# 5_PROFIBUS2.net
KiCad netlist of a schematic drawn in Altium Designer
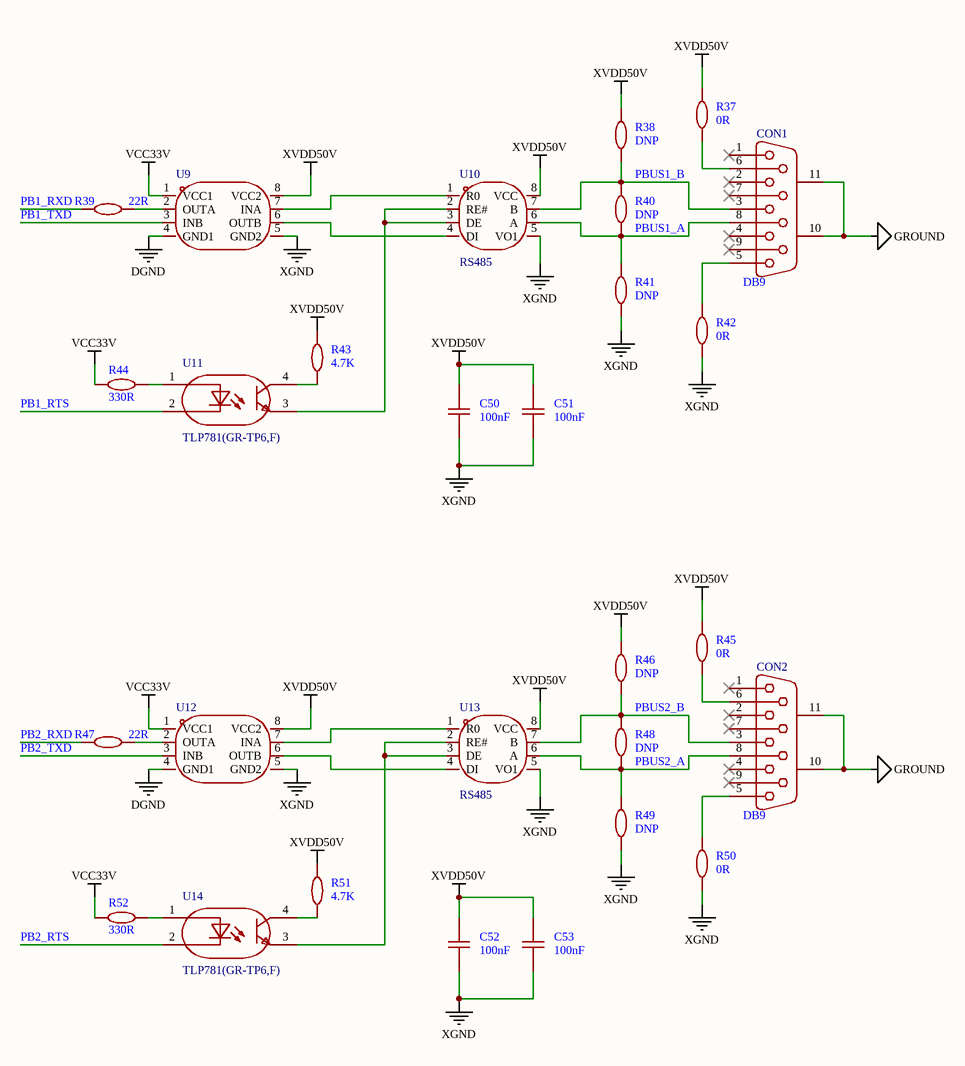
[diagram p0: 5_PROFIBUS2.schdoc]

(export (version "E")
  (design (tool "Eeschema 10.0.6"))
  (components
    (comp (ref "C50")
      (value "100nF")
      (footprint "C0402")
      (libsource (lib "altium-import") (part "root_1_CAP_0402_"))
    )
    (comp (ref "C51")
      (value "100nF")
      (footprint "C0402")
      (libsource (lib "altium-import") (part "root_1_CAP_0402_"))
    )
    (comp (ref "C52")
      (value "100nF")
      (footprint "C0402")
      (libsource (lib "altium-import") (part "root_1_CAP_0402_"))
    )
    (comp (ref "C53")
      (value "100nF")
      (footprint "C0402")
      (libsource (lib "altium-import") (part "root_1_CAP_0402_"))
    )
    (comp (ref "CON1")
      (value "DB9")
      (footprint "DB9-TH_DT10121-M5N3-4F")
      (libsource (lib "altium-import") (part "root_1_DB9 TH90_"))
    )
    (comp (ref "CON2")
      (value "DB9")
      (footprint "DB9-TH_DT10121-M5N3-4F")
      (libsource (lib "altium-import") (part "root_1_DB9 TH90_"))
    )
    (comp (ref "R37")
      (value "0R")
      (footprint "R0805")
      (libsource (lib "altium-import") (part "root_3_Res_0805_"))
    )
    (comp (ref "R38")
      (value "DNP")
      (footprint "R0805")
      (libsource (lib "altium-import") (part "root_1_Res_0805_"))
    )
    (comp (ref "R39")
      (value "22R")
      (footprint "R0402")
      (libsource (lib "altium-import") (part "root_0_Res_0402_"))
    )
    (comp (ref "R40")
      (value "DNP")
      (footprint "R0805")
      (libsource (lib "altium-import") (part "root_1_Res_0805_"))
    )
    (comp (ref "R41")
      (value "DNP")
      (footprint "R0805")
      (libsource (lib "altium-import") (part "root_1_Res_0805_"))
    )
    (comp (ref "R42")
      (value "0R")
      (footprint "R0805")
      (libsource (lib "altium-import") (part "root_1_Res_0805_"))
    )
    (comp (ref "R43")
      (value "4.7K")
      (footprint "R0402")
      (libsource (lib "altium-import") (part "root_1_Res_0402_"))
    )
    (comp (ref "R44")
      (value "330R")
      (footprint "R0402")
      (libsource (lib "altium-import") (part "root_0_Res_0402_"))
    )
    (comp (ref "R45")
      (value "0R")
      (footprint "R0805")
      (libsource (lib "altium-import") (part "root_3_Res_0805_"))
    )
    (comp (ref "R46")
      (value "DNP")
      (footprint "R0805")
      (libsource (lib "altium-import") (part "root_1_Res_0805_"))
    )
    (comp (ref "R47")
      (value "22R")
      (footprint "R0402")
      (libsource (lib "altium-import") (part "root_0_Res_0402_"))
    )
    (comp (ref "R48")
      (value "DNP")
      (footprint "R0805")
      (libsource (lib "altium-import") (part "root_1_Res_0805_"))
    )
    (comp (ref "R49")
      (value "DNP")
      (footprint "R0805")
      (libsource (lib "altium-import") (part "root_1_Res_0805_"))
    )
    (comp (ref "R50")
      (value "0R")
      (footprint "R0805")
      (libsource (lib "altium-import") (part "root_1_Res_0805_"))
    )
    (comp (ref "R51")
      (value "4.7K")
      (footprint "R0402")
      (libsource (lib "altium-import") (part "root_1_Res_0402_"))
    )
    (comp (ref "R52")
      (value "330R")
      (footprint "R0402")
      (libsource (lib "altium-import") (part "root_0_Res_0402_"))
    )
    (comp (ref "U9")
      (value "~")
      (footprint "SOIC-8_L5.0-W4.0-P1.27-LS6.0-BL")
      (libsource (lib "altium-import") (part "root_0_ISO7221AD_"))
    )
    (comp (ref "U10")
      (value "~")
      (footprint "SOP-8_L4.9-W3.9-P1.27-LS6.0-BL")
      (fields (field (name "DEVICE") "RS485"))
      (libsource (lib "altium-import") (part "root_0_RS485_"))
    )
    (comp (ref "U11")
      (value "~")
      (footprint "SOP-4_L6.5-W4.6-P2.54-LS10.3-TL")
      (fields (field (name "DEVICE") "TLP781(GR-TP6,F)"))
      (libsource (lib "altium-import") (part "root_0_TLP781(GR-TP6,F)_"))
    )
    (comp (ref "U12")
      (value "~")
      (footprint "SOIC-8_L5.0-W4.0-P1.27-LS6.0-BL")
      (libsource (lib "altium-import") (part "root_0_ISO7221AD_"))
    )
    (comp (ref "U13")
      (value "~")
      (footprint "SOP-8_L4.9-W3.9-P1.27-LS6.0-BL")
      (fields (field (name "DEVICE") "RS485"))
      (libsource (lib "altium-import") (part "root_0_RS485_"))
    )
    (comp (ref "U14")
      (value "~")
      (footprint "SOP-4_L6.5-W4.6-P2.54-LS10.3-TL")
      (fields (field (name "DEVICE") "TLP781(GR-TP6,F)"))
      (libsource (lib "altium-import") (part "root_0_TLP781(GR-TP6,F)_"))
    )
  )
  (nets
    (net (code "1") (name "/PB1_RTS") (class "Default")
      (node (ref "U11") (pin "2") (pinfunction "2_2") (pintype "passive"))
    )
    (net (code "2") (name "/PB1_RXD") (class "Default")
      (node (ref "R39") (pin "1") (pinfunction "1_1") (pintype "passive"))
    )
    (net (code "3") (name "/PB1_TXD") (class "Default")
      (node (ref "U9") (pin "3") (pinfunction "INB_3") (pintype "passive"))
    )
    (net (code "4") (name "/PB2_RTS") (class "Default")
      (node (ref "U14") (pin "2") (pinfunction "2_2") (pintype "passive"))
    )
    (net (code "5") (name "/PB2_RXD") (class "Default")
      (node (ref "R47") (pin "1") (pinfunction "1_1") (pintype "passive"))
    )
    (net (code "6") (name "/PB2_TXD") (class "Default")
      (node (ref "U12") (pin "3") (pinfunction "INB_3") (pintype "passive"))
    )
    (net (code "7") (name "/PBUS1_A") (class "Default")
      (node (ref "CON1") (pin "8") (pinfunction "8_8") (pintype "passive"))
      (node (ref "R40") (pin "1") (pinfunction "1_1") (pintype "passive"))
      (node (ref "R41") (pin "2") (pinfunction "2_2") (pintype "passive"))
      (node (ref "U10") (pin "6") (pinfunction "A_6") (pintype "passive"))
    )
    (net (code "8") (name "/PBUS1_B") (class "Default")
      (node (ref "CON1") (pin "3") (pinfunction "3_3") (pintype "passive"))
      (node (ref "R38") (pin "1") (pinfunction "1_1") (pintype "passive"))
      (node (ref "R40") (pin "2") (pinfunction "2_2") (pintype "passive"))
      (node (ref "U10") (pin "7") (pinfunction "B_7") (pintype "passive"))
    )
    (net (code "9") (name "/PBUS2_A") (class "Default")
      (node (ref "CON2") (pin "8") (pinfunction "8_8") (pintype "passive"))
      (node (ref "R48") (pin "1") (pinfunction "1_1") (pintype "passive"))
      (node (ref "R49") (pin "2") (pinfunction "2_2") (pintype "passive"))
      (node (ref "U13") (pin "6") (pinfunction "A_6") (pintype "passive"))
    )
    (net (code "10") (name "/PBUS2_B") (class "Default")
      (node (ref "CON2") (pin "3") (pinfunction "3_3") (pintype "passive"))
      (node (ref "R46") (pin "1") (pinfunction "1_1") (pintype "passive"))
      (node (ref "R48") (pin "2") (pinfunction "2_2") (pintype "passive"))
      (node (ref "U13") (pin "7") (pinfunction "B_7") (pintype "passive"))
    )
    (net (code "11") (name "DGND") (class "Default")
      (node (ref "U12") (pin "4") (pinfunction "GND1_4") (pintype "passive"))
      (node (ref "U9") (pin "4") (pinfunction "GND1_4") (pintype "passive"))
    )
    (net (code "12") (name "GROUND") (class "Default")
      (node (ref "CON1") (pin "10") (pinfunction "MH1_10") (pintype "passive"))
      (node (ref "CON1") (pin "11") (pinfunction "MH2_11") (pintype "passive"))
      (node (ref "CON2") (pin "10") (pinfunction "MH1_10") (pintype "passive"))
      (node (ref "CON2") (pin "11") (pinfunction "MH2_11") (pintype "passive"))
    )
    (net (code "13") (name "Net-(CON1-Pad5)") (class "Default")
      (node (ref "CON1") (pin "5") (pinfunction "5_5") (pintype "passive"))
      (node (ref "R42") (pin "2") (pinfunction "2_2") (pintype "passive"))
    )
    (net (code "14") (name "Net-(CON1-Pad6)") (class "Default")
      (node (ref "CON1") (pin "6") (pinfunction "6_6") (pintype "passive"))
      (node (ref "R37") (pin "2") (pinfunction "2_2") (pintype "passive"))
    )
    (net (code "15") (name "Net-(CON2-Pad5)") (class "Default")
      (node (ref "CON2") (pin "5") (pinfunction "5_5") (pintype "passive"))
      (node (ref "R50") (pin "2") (pinfunction "2_2") (pintype "passive"))
    )
    (net (code "16") (name "Net-(CON2-Pad6)") (class "Default")
      (node (ref "CON2") (pin "6") (pinfunction "6_6") (pintype "passive"))
      (node (ref "R45") (pin "2") (pinfunction "2_2") (pintype "passive"))
    )
    (net (code "17") (name "Net-(R43-Pad1)") (class "Default")
      (node (ref "R43") (pin "1") (pinfunction "1_1") (pintype "passive"))
      (node (ref "U11") (pin "4") (pinfunction "4_4") (pintype "passive"))
    )
    (net (code "18") (name "Net-(R44-Pad2)") (class "Default")
      (node (ref "R44") (pin "2") (pinfunction "2_2") (pintype "passive"))
      (node (ref "U11") (pin "1") (pinfunction "1_1") (pintype "passive"))
    )
    (net (code "19") (name "Net-(R51-Pad1)") (class "Default")
      (node (ref "R51") (pin "1") (pinfunction "1_1") (pintype "passive"))
      (node (ref "U14") (pin "4") (pinfunction "4_4") (pintype "passive"))
    )
    (net (code "20") (name "Net-(R52-Pad2)") (class "Default")
      (node (ref "R52") (pin "2") (pinfunction "2_2") (pintype "passive"))
      (node (ref "U14") (pin "1") (pinfunction "1_1") (pintype "passive"))
    )
    (net (code "21") (name "Net-(U9-OUTA)") (class "Default")
      (node (ref "R39") (pin "2") (pinfunction "2_2") (pintype "passive"))
      (node (ref "U9") (pin "2") (pinfunction "OUTA_2") (pintype "passive"))
    )
    (net (code "22") (name "Net-(U10-DE)") (class "Default")
      (node (ref "U10") (pin "2") (pinfunction "RE#_2") (pintype "passive"))
      (node (ref "U10") (pin "3") (pinfunction "DE_3") (pintype "passive"))
      (node (ref "U11") (pin "3") (pinfunction "3_3") (pintype "passive"))
    )
    (net (code "23") (name "Net-(U10-DI)") (class "Default")
      (node (ref "U10") (pin "4") (pinfunction "DI_4") (pintype "passive"))
      (node (ref "U9") (pin "6") (pinfunction "OUTB_6") (pintype "passive"))
    )
    (net (code "24") (name "Net-(U10-R0)") (class "Default")
      (node (ref "U10") (pin "1") (pinfunction "R0_1") (pintype "passive"))
      (node (ref "U9") (pin "7") (pinfunction "INA_7") (pintype "passive"))
    )
    (net (code "25") (name "Net-(U12-INA)") (class "Default")
      (node (ref "U12") (pin "7") (pinfunction "INA_7") (pintype "passive"))
      (node (ref "U13") (pin "1") (pinfunction "R0_1") (pintype "passive"))
    )
    (net (code "26") (name "Net-(U12-OUTA)") (class "Default")
      (node (ref "R47") (pin "2") (pinfunction "2_2") (pintype "passive"))
      (node (ref "U12") (pin "2") (pinfunction "OUTA_2") (pintype "passive"))
    )
    (net (code "27") (name "Net-(U12-OUTB)") (class "Default")
      (node (ref "U12") (pin "6") (pinfunction "OUTB_6") (pintype "passive"))
      (node (ref "U13") (pin "4") (pinfunction "DI_4") (pintype "passive"))
    )
    (net (code "28") (name "Net-(U13-DE)") (class "Default")
      (node (ref "U13") (pin "2") (pinfunction "RE#_2") (pintype "passive"))
      (node (ref "U13") (pin "3") (pinfunction "DE_3") (pintype "passive"))
      (node (ref "U14") (pin "3") (pinfunction "3_3") (pintype "passive"))
    )
    (net (code "29") (name "VCC33V") (class "Default")
      (node (ref "R44") (pin "1") (pinfunction "1_1") (pintype "passive"))
      (node (ref "R52") (pin "1") (pinfunction "1_1") (pintype "passive"))
      (node (ref "U12") (pin "1") (pinfunction "VCC1_1") (pintype "passive"))
      (node (ref "U9") (pin "1") (pinfunction "VCC1_1") (pintype "passive"))
    )
    (net (code "30") (name "XGND") (class "Default")
      (node (ref "C50") (pin "1") (pinfunction "1_1") (pintype "passive"))
      (node (ref "C51") (pin "1") (pinfunction "1_1") (pintype "passive"))
      (node (ref "C52") (pin "1") (pinfunction "1_1") (pintype "passive"))
      (node (ref "C53") (pin "1") (pinfunction "1_1") (pintype "passive"))
      (node (ref "R41") (pin "1") (pinfunction "1_1") (pintype "passive"))
      (node (ref "R42") (pin "1") (pinfunction "1_1") (pintype "passive"))
      (node (ref "R49") (pin "1") (pinfunction "1_1") (pintype "passive"))
      (node (ref "R50") (pin "1") (pinfunction "1_1") (pintype "passive"))
      (node (ref "U10") (pin "5") (pinfunction "VO1_5") (pintype "passive"))
      (node (ref "U12") (pin "5") (pinfunction "GND2_5") (pintype "passive"))
      (node (ref "U13") (pin "5") (pinfunction "VO1_5") (pintype "passive"))
      (node (ref "U9") (pin "5") (pinfunction "GND2_5") (pintype "passive"))
    )
    (net (code "31") (name "XVDD50V") (class "Default")
      (node (ref "C50") (pin "2") (pinfunction "2_2") (pintype "passive"))
      (node (ref "C51") (pin "2") (pinfunction "2_2") (pintype "passive"))
      (node (ref "C52") (pin "2") (pinfunction "2_2") (pintype "passive"))
      (node (ref "C53") (pin "2") (pinfunction "2_2") (pintype "passive"))
      (node (ref "R37") (pin "1") (pinfunction "1_1") (pintype "passive"))
      (node (ref "R38") (pin "2") (pinfunction "2_2") (pintype "passive"))
      (node (ref "R43") (pin "2") (pinfunction "2_2") (pintype "passive"))
      (node (ref "R45") (pin "1") (pinfunction "1_1") (pintype "passive"))
      (node (ref "R46") (pin "2") (pinfunction "2_2") (pintype "passive"))
      (node (ref "R51") (pin "2") (pinfunction "2_2") (pintype "passive"))
      (node (ref "U10") (pin "8") (pinfunction "VCC_8") (pintype "passive"))
      (node (ref "U12") (pin "8") (pinfunction "VCC2_8") (pintype "passive"))
      (node (ref "U13") (pin "8") (pinfunction "VCC_8") (pintype "passive"))
      (node (ref "U9") (pin "8") (pinfunction "VCC2_8") (pintype "passive"))
    )
    (net (code "32") (name "unconnected-(CON1-Pad1)") (class "Default")
      (node (ref "CON1") (pin "1") (pinfunction "1_1") (pintype "passive+no_connect"))
    )
    (net (code "33") (name "unconnected-(CON1-Pad2)") (class "Default")
      (node (ref "CON1") (pin "2") (pinfunction "2_2") (pintype "passive+no_connect"))
    )
    (net (code "34") (name "unconnected-(CON1-Pad4)") (class "Default")
      (node (ref "CON1") (pin "4") (pinfunction "4_4") (pintype "passive+no_connect"))
    )
    (net (code "35") (name "unconnected-(CON1-Pad7)") (class "Default")
      (node (ref "CON1") (pin "7") (pinfunction "7_7") (pintype "passive+no_connect"))
    )
    (net (code "36") (name "unconnected-(CON1-Pad9)") (class "Default")
      (node (ref "CON1") (pin "9") (pinfunction "9_9") (pintype "passive+no_connect"))
    )
    (net (code "37") (name "unconnected-(CON2-Pad1)") (class "Default")
      (node (ref "CON2") (pin "1") (pinfunction "1_1") (pintype "passive+no_connect"))
    )
    (net (code "38") (name "unconnected-(CON2-Pad2)") (class "Default")
      (node (ref "CON2") (pin "2") (pinfunction "2_2") (pintype "passive+no_connect"))
    )
    (net (code "39") (name "unconnected-(CON2-Pad4)") (class "Default")
      (node (ref "CON2") (pin "4") (pinfunction "4_4") (pintype "passive+no_connect"))
    )
    (net (code "40") (name "unconnected-(CON2-Pad7)") (class "Default")
      (node (ref "CON2") (pin "7") (pinfunction "7_7") (pintype "passive+no_connect"))
    )
    (net (code "41") (name "unconnected-(CON2-Pad9)") (class "Default")
      (node (ref "CON2") (pin "9") (pinfunction "9_9") (pintype "passive+no_connect"))
    )
  )
)
